# LiFePo4_Charger_Single_to_Chain_--_Finis.net
KiCad netlist of a schematic drawn in EAGLE
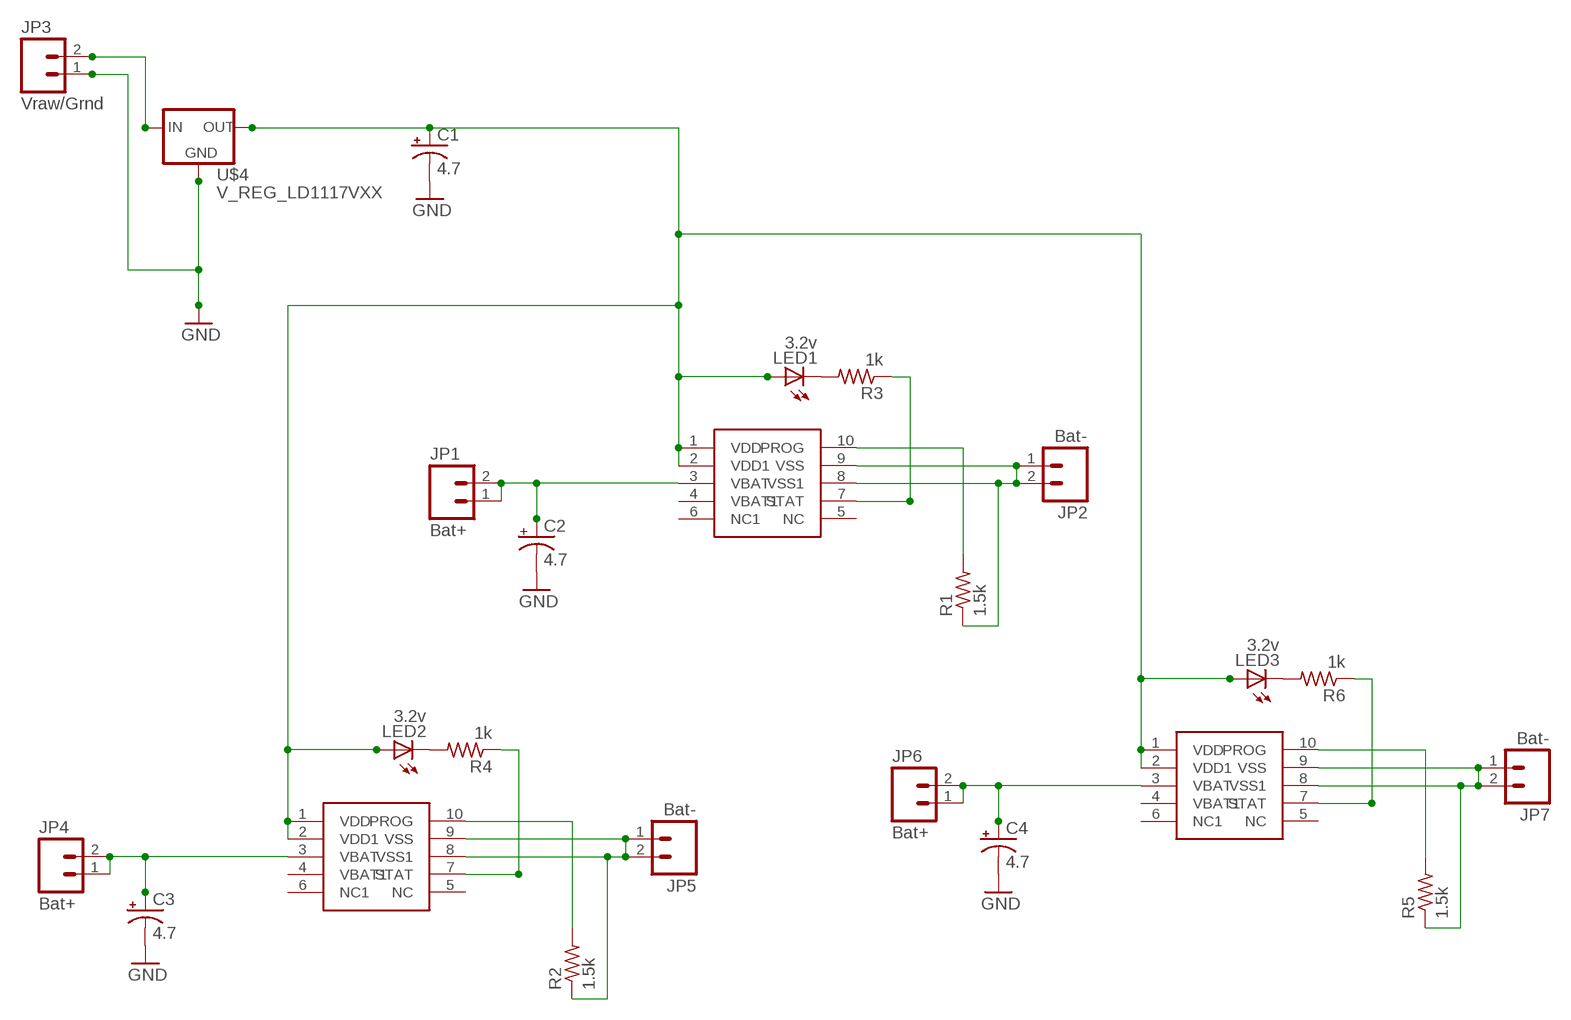
[diagram p0: schematic, sheet 1]

(export (version "E")
  (design (tool "Eeschema 10.0.6"))
  (components
    (comp (ref "C1")
      (value "4.7")
      (footprint "eagle-import:CPOL-RADIAL-10UF-25V")
      (libsource (lib "eagle-import") (part "CAP_POLPTH2"))
    )
    (comp (ref "C2")
      (value "4.7")
      (footprint "eagle-import:CPOL-RADIAL-10UF-25V")
      (libsource (lib "eagle-import") (part "CAP_POLPTH2"))
    )
    (comp (ref "C3")
      (value "4.7")
      (footprint "eagle-import:CPOL-RADIAL-10UF-25V")
      (libsource (lib "eagle-import") (part "CAP_POLPTH2"))
    )
    (comp (ref "C4")
      (value "4.7")
      (footprint "eagle-import:CPOL-RADIAL-10UF-25V")
      (libsource (lib "eagle-import") (part "CAP_POLPTH2"))
    )
    (comp (ref "JP1")
      (value "Bat+")
      (footprint "eagle-import:1X02")
      (libsource (lib "eagle-import") (part "M02PTH"))
    )
    (comp (ref "JP2")
      (value "Bat-")
      (footprint "eagle-import:1X02")
      (libsource (lib "eagle-import") (part "M02PTH"))
    )
    (comp (ref "JP3")
      (value "Vraw/Grnd")
      (footprint "eagle-import:1X02")
      (libsource (lib "eagle-import") (part "M02PTH"))
    )
    (comp (ref "JP4")
      (value "Bat+")
      (footprint "eagle-import:1X02")
      (libsource (lib "eagle-import") (part "M02PTH"))
    )
    (comp (ref "JP5")
      (value "Bat-")
      (footprint "eagle-import:1X02")
      (libsource (lib "eagle-import") (part "M02PTH"))
    )
    (comp (ref "JP6")
      (value "Bat+")
      (footprint "eagle-import:1X02")
      (libsource (lib "eagle-import") (part "M02PTH"))
    )
    (comp (ref "JP7")
      (value "Bat-")
      (footprint "eagle-import:1X02")
      (libsource (lib "eagle-import") (part "M02PTH"))
    )
    (comp (ref "LED1")
      (value "3.2v")
      (footprint "eagle-import:LED3MM")
      (libsource (lib "eagle-import") (part "LED3MM"))
    )
    (comp (ref "LED2")
      (value "3.2v")
      (footprint "eagle-import:LED3MM")
      (libsource (lib "eagle-import") (part "LED3MM"))
    )
    (comp (ref "LED3")
      (value "3.2v")
      (footprint "eagle-import:LED3MM")
      (libsource (lib "eagle-import") (part "LED3MM"))
    )
    (comp (ref "R1")
      (value "1.5k")
      (footprint "eagle-import:0204_7")
      (libsource (lib "eagle-import") (part "R-US_0204/7"))
    )
    (comp (ref "R2")
      (value "1.5k")
      (footprint "eagle-import:0204_7")
      (libsource (lib "eagle-import") (part "R-US_0204/7"))
    )
    (comp (ref "R3")
      (value "1k")
      (footprint "eagle-import:0204_7")
      (libsource (lib "eagle-import") (part "R-US_0204/7"))
    )
    (comp (ref "R4")
      (value "1k")
      (footprint "eagle-import:0204_7")
      (libsource (lib "eagle-import") (part "R-US_0204/7"))
    )
    (comp (ref "R5")
      (value "1.5k")
      (footprint "eagle-import:0204_7")
      (libsource (lib "eagle-import") (part "R-US_0204/7"))
    )
    (comp (ref "R6")
      (value "1k")
      (footprint "eagle-import:0204_7")
      (libsource (lib "eagle-import") (part "R-US_0204/7"))
    )
    (comp (ref "U$1")
      (value "MCP73123/223")
      (footprint "eagle-import:MCP73123_223")
      (libsource (lib "eagle-import") (part "MCP73123/223"))
    )
    (comp (ref "U$2")
      (value "MCP73123/223")
      (footprint "eagle-import:MCP73123_223")
      (libsource (lib "eagle-import") (part "MCP73123/223"))
    )
    (comp (ref "U$4")
      (value "V_REG_LD1117VXX")
      (footprint "eagle-import:78XXL")
      (libsource (lib "eagle-import") (part "V_REG_LD1117VXX"))
    )
    (comp (ref "U$8")
      (value "MCP73123/223")
      (footprint "eagle-import:MCP73123_223")
      (libsource (lib "eagle-import") (part "MCP73123/223"))
    )
  )
  (nets
    (net (code "1") (name "GND") (class "Default")
      (node (ref "C1") (pin "2") (pinfunction "-_2") (pintype "passive"))
      (node (ref "C2") (pin "2") (pinfunction "-_2") (pintype "passive"))
      (node (ref "C3") (pin "2") (pinfunction "-_2") (pintype "passive"))
      (node (ref "C4") (pin "2") (pinfunction "-_2") (pintype "passive"))
      (node (ref "JP3") (pin "1") (pinfunction "1_1") (pintype "passive"))
      (node (ref "U$4") (pin "IN") (pinfunction "GND_IN") (pintype "input"))
    )
    (net (code "2") (name "Net-(C1-+)") (class "Default")
      (node (ref "C1") (pin "1") (pinfunction "+_1") (pintype "passive"))
      (node (ref "LED1") (pin "A") (pinfunction "A_A") (pintype "passive"))
      (node (ref "LED2") (pin "A") (pinfunction "A_A") (pintype "passive"))
      (node (ref "LED3") (pin "A") (pinfunction "A_A") (pintype "passive"))
      (node (ref "U$1") (pin "1") (pinfunction "VDD_1") (pintype "bidirectional"))
      (node (ref "U$1") (pin "2") (pinfunction "VDD1_2") (pintype "bidirectional"))
      (node (ref "U$2") (pin "1") (pinfunction "VDD_1") (pintype "bidirectional"))
      (node (ref "U$2") (pin "2") (pinfunction "VDD1_2") (pintype "bidirectional"))
      (node (ref "U$4") (pin "GND") (pinfunction "OUT_GND") (pintype "output"))
      (node (ref "U$8") (pin "1") (pinfunction "VDD_1") (pintype "bidirectional"))
      (node (ref "U$8") (pin "2") (pinfunction "VDD1_2") (pintype "bidirectional"))
    )
    (net (code "3") (name "Net-(C2-+)") (class "Default")
      (node (ref "C2") (pin "1") (pinfunction "+_1") (pintype "passive"))
      (node (ref "JP1") (pin "1") (pinfunction "1_1") (pintype "passive"))
      (node (ref "JP1") (pin "2") (pinfunction "2_2") (pintype "passive"))
      (node (ref "U$8") (pin "3") (pinfunction "VBAT_3") (pintype "bidirectional"))
    )
    (net (code "4") (name "Net-(C3-+)") (class "Default")
      (node (ref "C3") (pin "1") (pinfunction "+_1") (pintype "passive"))
      (node (ref "JP4") (pin "1") (pinfunction "1_1") (pintype "passive"))
      (node (ref "JP4") (pin "2") (pinfunction "2_2") (pintype "passive"))
      (node (ref "U$1") (pin "3") (pinfunction "VBAT_3") (pintype "bidirectional"))
    )
    (net (code "5") (name "Net-(C4-+)") (class "Default")
      (node (ref "C4") (pin "1") (pinfunction "+_1") (pintype "passive"))
      (node (ref "JP6") (pin "1") (pinfunction "1_1") (pintype "passive"))
      (node (ref "JP6") (pin "2") (pinfunction "2_2") (pintype "passive"))
      (node (ref "U$2") (pin "3") (pinfunction "VBAT_3") (pintype "bidirectional"))
    )
    (net (code "6") (name "Net-(LED1-C)") (class "Default")
      (node (ref "LED1") (pin "K") (pinfunction "C_K") (pintype "passive"))
      (node (ref "R3") (pin "2") (pinfunction "2_2") (pintype "passive"))
    )
    (net (code "7") (name "Net-(LED2-C)") (class "Default")
      (node (ref "LED2") (pin "K") (pinfunction "C_K") (pintype "passive"))
      (node (ref "R4") (pin "2") (pinfunction "2_2") (pintype "passive"))
    )
    (net (code "8") (name "Net-(LED3-C)") (class "Default")
      (node (ref "LED3") (pin "K") (pinfunction "C_K") (pintype "passive"))
      (node (ref "R6") (pin "2") (pinfunction "2_2") (pintype "passive"))
    )
    (net (code "9") (name "Net-(U$1-PROG)") (class "Default")
      (node (ref "R2") (pin "2") (pinfunction "2_2") (pintype "passive"))
      (node (ref "U$1") (pin "10") (pinfunction "PROG_10") (pintype "bidirectional"))
    )
    (net (code "10") (name "Net-(U$1-STAT)") (class "Default")
      (node (ref "R4") (pin "1") (pinfunction "1_1") (pintype "passive"))
      (node (ref "U$1") (pin "7") (pinfunction "STAT_7") (pintype "bidirectional"))
    )
    (net (code "11") (name "Net-(U$1-VSS)") (class "Default")
      (node (ref "JP5") (pin "1") (pinfunction "1_1") (pintype "passive"))
      (node (ref "JP5") (pin "2") (pinfunction "2_2") (pintype "passive"))
      (node (ref "R2") (pin "1") (pinfunction "1_1") (pintype "passive"))
      (node (ref "U$1") (pin "8") (pinfunction "VSS1_8") (pintype "bidirectional"))
      (node (ref "U$1") (pin "9") (pinfunction "VSS_9") (pintype "bidirectional"))
    )
    (net (code "12") (name "Net-(U$2-PROG)") (class "Default")
      (node (ref "R5") (pin "2") (pinfunction "2_2") (pintype "passive"))
      (node (ref "U$2") (pin "10") (pinfunction "PROG_10") (pintype "bidirectional"))
    )
    (net (code "13") (name "Net-(U$2-STAT)") (class "Default")
      (node (ref "R6") (pin "1") (pinfunction "1_1") (pintype "passive"))
      (node (ref "U$2") (pin "7") (pinfunction "STAT_7") (pintype "bidirectional"))
    )
    (net (code "14") (name "Net-(U$2-VSS)") (class "Default")
      (node (ref "JP7") (pin "1") (pinfunction "1_1") (pintype "passive"))
      (node (ref "JP7") (pin "2") (pinfunction "2_2") (pintype "passive"))
      (node (ref "R5") (pin "1") (pinfunction "1_1") (pintype "passive"))
      (node (ref "U$2") (pin "8") (pinfunction "VSS1_8") (pintype "bidirectional"))
      (node (ref "U$2") (pin "9") (pinfunction "VSS_9") (pintype "bidirectional"))
    )
    (net (code "15") (name "Net-(U$4-IN)") (class "Default")
      (node (ref "JP3") (pin "2") (pinfunction "2_2") (pintype "passive"))
      (node (ref "U$4") (pin "OUT") (pinfunction "IN_OUT") (pintype "input"))
    )
    (net (code "16") (name "Net-(U$8-PROG)") (class "Default")
      (node (ref "R1") (pin "2") (pinfunction "2_2") (pintype "passive"))
      (node (ref "U$8") (pin "10") (pinfunction "PROG_10") (pintype "bidirectional"))
    )
    (net (code "17") (name "Net-(U$8-STAT)") (class "Default")
      (node (ref "R3") (pin "1") (pinfunction "1_1") (pintype "passive"))
      (node (ref "U$8") (pin "7") (pinfunction "STAT_7") (pintype "bidirectional"))
    )
    (net (code "18") (name "Net-(U$8-VSS)") (class "Default")
      (node (ref "JP2") (pin "1") (pinfunction "1_1") (pintype "passive"))
      (node (ref "JP2") (pin "2") (pinfunction "2_2") (pintype "passive"))
      (node (ref "R1") (pin "1") (pinfunction "1_1") (pintype "passive"))
      (node (ref "U$8") (pin "8") (pinfunction "VSS1_8") (pintype "bidirectional"))
      (node (ref "U$8") (pin "9") (pinfunction "VSS_9") (pintype "bidirectional"))
    )
    (net (code "19") (name "unconnected-(U$1-NC-Pad5)") (class "Default")
      (node (ref "U$1") (pin "5") (pinfunction "NC_5") (pintype "bidirectional"))
    )
    (net (code "20") (name "unconnected-(U$1-NC1-Pad6)") (class "Default")
      (node (ref "U$1") (pin "6") (pinfunction "NC1_6") (pintype "bidirectional"))
    )
    (net (code "21") (name "unconnected-(U$1-VBAT1-Pad4)") (class "Default")
      (node (ref "U$1") (pin "4") (pinfunction "VBAT1_4") (pintype "bidirectional"))
    )
    (net (code "22") (name "unconnected-(U$2-NC-Pad5)") (class "Default")
      (node (ref "U$2") (pin "5") (pinfunction "NC_5") (pintype "bidirectional"))
    )
    (net (code "23") (name "unconnected-(U$2-NC1-Pad6)") (class "Default")
      (node (ref "U$2") (pin "6") (pinfunction "NC1_6") (pintype "bidirectional"))
    )
    (net (code "24") (name "unconnected-(U$2-VBAT1-Pad4)") (class "Default")
      (node (ref "U$2") (pin "4") (pinfunction "VBAT1_4") (pintype "bidirectional"))
    )
    (net (code "25") (name "unconnected-(U$8-NC-Pad5)") (class "Default")
      (node (ref "U$8") (pin "5") (pinfunction "NC_5") (pintype "bidirectional"))
    )
    (net (code "26") (name "unconnected-(U$8-NC1-Pad6)") (class "Default")
      (node (ref "U$8") (pin "6") (pinfunction "NC1_6") (pintype "bidirectional"))
    )
    (net (code "27") (name "unconnected-(U$8-VBAT1-Pad4)") (class "Default")
      (node (ref "U$8") (pin "4") (pinfunction "VBAT1_4") (pintype "bidirectional"))
    )
  )
)
